# CMP_1_1.net
KiCad netlist of a schematic drawn in EAGLE
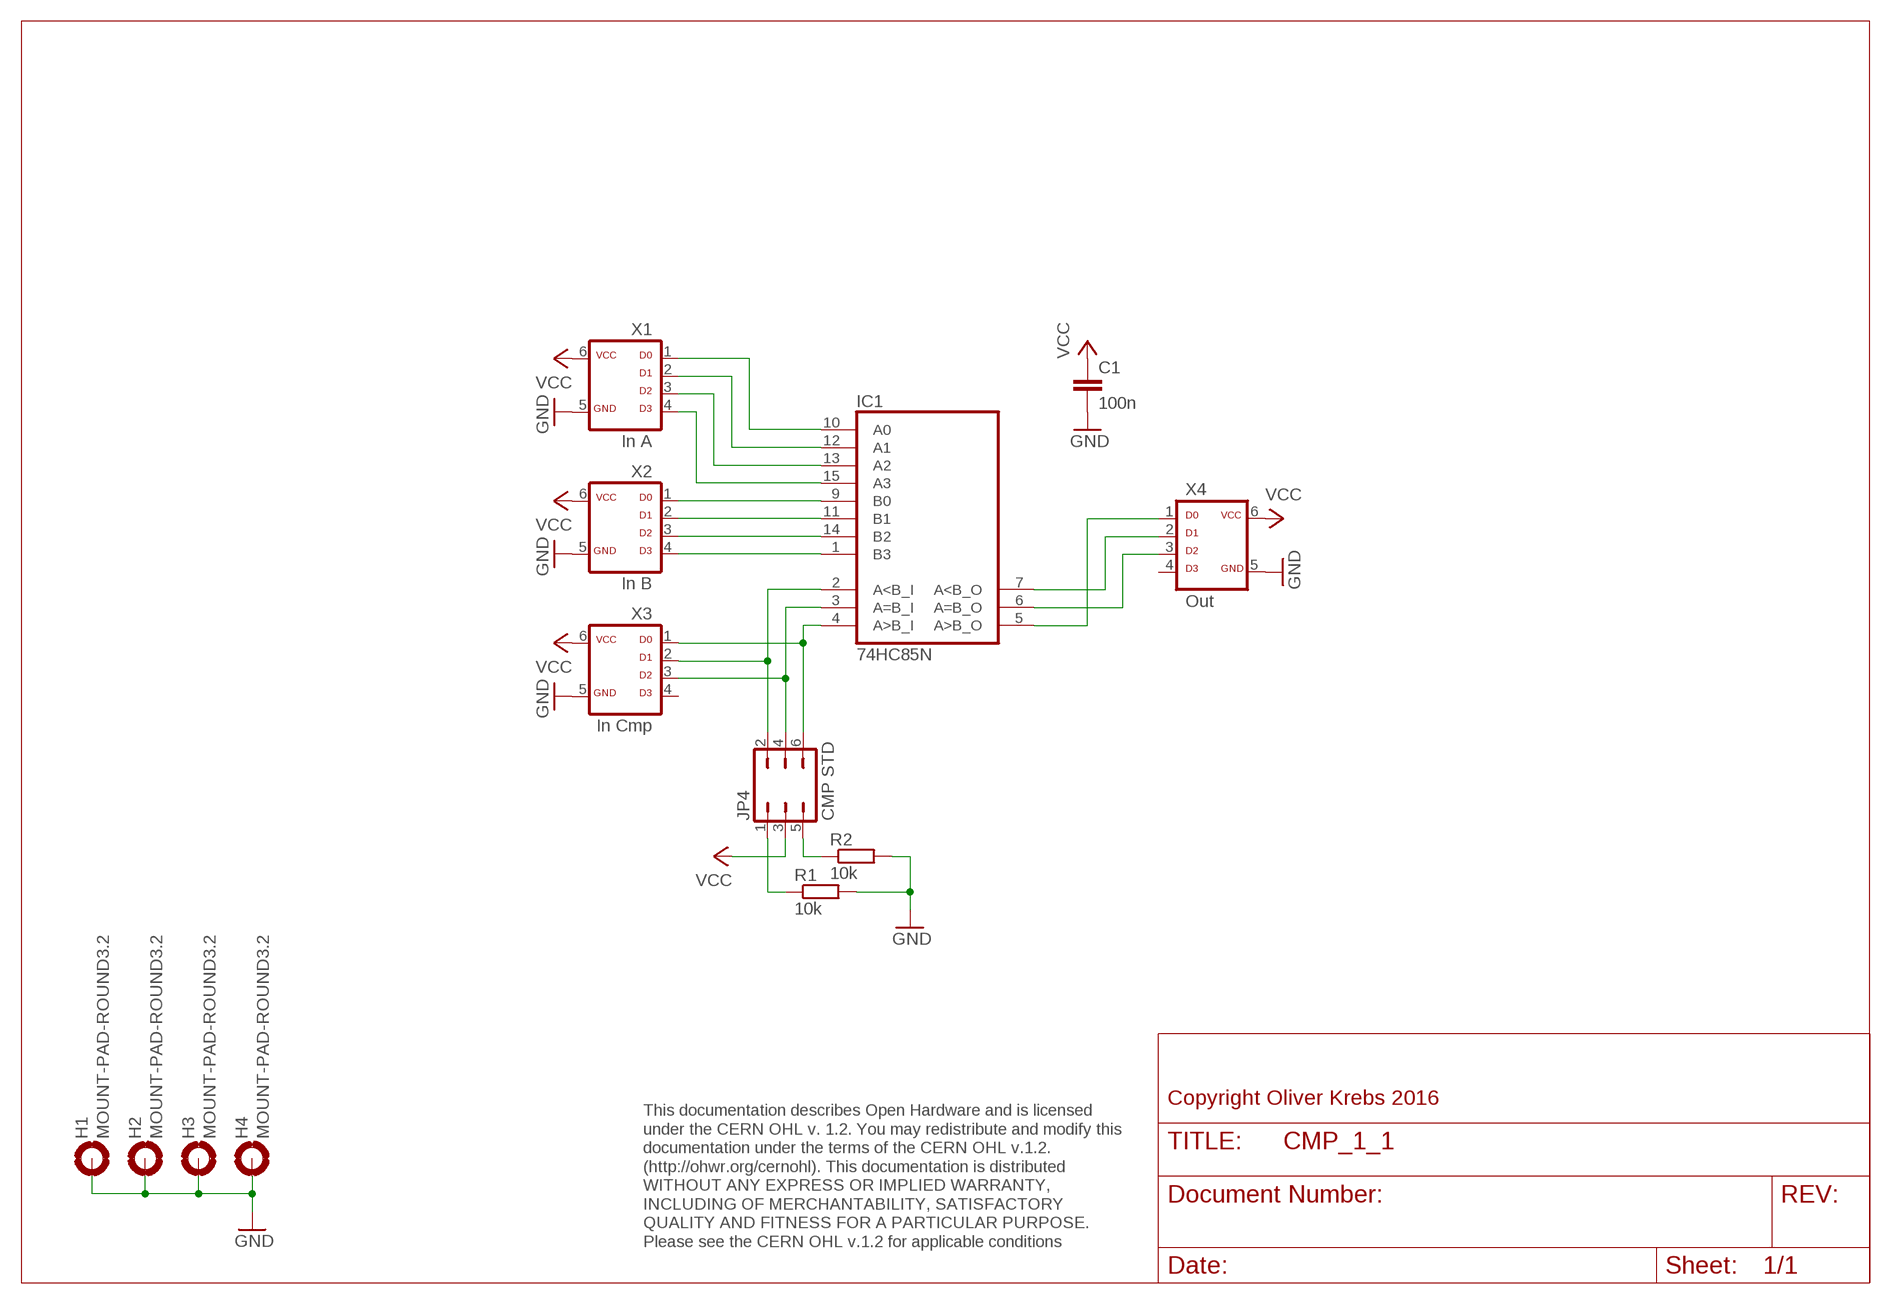
[diagram p0: schematic, sheet 1]

(export (version "E")
  (design (tool "Eeschema 10.0.6"))
  (components
    (comp (ref "C1")
      (value "100n")
      (footprint "eagle-import:C050-025X075")
      (libsource (lib "eagle-import") (part "C-EU050-025X075"))
    )
    (comp (ref "H1")
      (value "MOUNT-PAD-ROUND3.2")
      (footprint "eagle-import:3,2-PAD")
      (libsource (lib "eagle-import") (part "MOUNT-PAD-ROUND3.2"))
    )
    (comp (ref "H2")
      (value "MOUNT-PAD-ROUND3.2")
      (footprint "eagle-import:3,2-PAD")
      (libsource (lib "eagle-import") (part "MOUNT-PAD-ROUND3.2"))
    )
    (comp (ref "H3")
      (value "MOUNT-PAD-ROUND3.2")
      (footprint "eagle-import:3,2-PAD")
      (libsource (lib "eagle-import") (part "MOUNT-PAD-ROUND3.2"))
    )
    (comp (ref "H4")
      (value "MOUNT-PAD-ROUND3.2")
      (footprint "eagle-import:3,2-PAD")
      (libsource (lib "eagle-import") (part "MOUNT-PAD-ROUND3.2"))
    )
    (comp (ref "IC1")
      (value "74HC85N")
      (footprint "eagle-import:DIL16")
      (libsource (lib "eagle-import") (part "7485NHC"))
    )
    (comp (ref "JP4")
      (value "CMP STD")
      (footprint "eagle-import:JP3Q")
      (libsource (lib "eagle-import") (part "JP3Q"))
    )
    (comp (ref "R1")
      (value "10k")
      (footprint "eagle-import:0207_10")
      (libsource (lib "eagle-import") (part "R-EU_0207/10"))
    )
    (comp (ref "R2")
      (value "10k")
      (footprint "eagle-import:0207_10")
      (libsource (lib "eagle-import") (part "R-EU_0207/10"))
    )
    (comp (ref "X1")
      (value "In A")
      (footprint "eagle-import:ML-6")
      (libsource (lib "eagle-import") (part "ML6D"))
    )
    (comp (ref "X2")
      (value "In B")
      (footprint "eagle-import:ML-6")
      (libsource (lib "eagle-import") (part "ML6D"))
    )
    (comp (ref "X3")
      (value "In Cmp")
      (footprint "eagle-import:ML-6")
      (libsource (lib "eagle-import") (part "ML6D"))
    )
    (comp (ref "X4")
      (value "Out")
      (footprint "eagle-import:ML-6")
      (libsource (lib "eagle-import") (part "ML6D"))
    )
  )
  (nets
    (net (code "1") (name "GND") (class "Default")
      (node (ref "C1") (pin "2") (pinfunction "2_2") (pintype "passive"))
      (node (ref "H1") (pin "B3,2") (pinfunction "MOUNT_B3,2") (pintype "passive"))
      (node (ref "H2") (pin "B3,2") (pinfunction "MOUNT_B3,2") (pintype "passive"))
      (node (ref "H3") (pin "B3,2") (pinfunction "MOUNT_B3,2") (pintype "passive"))
      (node (ref "H4") (pin "B3,2") (pinfunction "MOUNT_B3,2") (pintype "passive"))
      (node (ref "R1") (pin "2") (pinfunction "2_2") (pintype "passive"))
      (node (ref "R2") (pin "2") (pinfunction "2_2") (pintype "passive"))
      (node (ref "X1") (pin "5") (pinfunction "5_5") (pintype "passive"))
      (node (ref "X2") (pin "5") (pinfunction "5_5") (pintype "passive"))
      (node (ref "X3") (pin "5") (pinfunction "5_5") (pintype "passive"))
      (node (ref "X4") (pin "5") (pinfunction "5_5") (pintype "passive"))
    )
    (net (code "2") (name "Net-(IC1A-A0)") (class "Default")
      (node (ref "IC1") (pin "10") (pinfunction "A0_10") (pintype "input"))
      (node (ref "X1") (pin "1") (pinfunction "1_1") (pintype "passive"))
    )
    (net (code "3") (name "Net-(IC1A-A1)") (class "Default")
      (node (ref "IC1") (pin "12") (pinfunction "A1_12") (pintype "input"))
      (node (ref "X1") (pin "2") (pinfunction "2_2") (pintype "passive"))
    )
    (net (code "4") (name "Net-(IC1A-A2)") (class "Default")
      (node (ref "IC1") (pin "13") (pinfunction "A2_13") (pintype "input"))
      (node (ref "X1") (pin "3") (pinfunction "3_3") (pintype "passive"))
    )
    (net (code "5") (name "Net-(IC1A-A3)") (class "Default")
      (node (ref "IC1") (pin "15") (pinfunction "A3_15") (pintype "input"))
      (node (ref "X1") (pin "4") (pinfunction "4_4") (pintype "passive"))
    )
    (net (code "6") (name "Net-(IC1A-A<B_I)") (class "Default")
      (node (ref "IC1") (pin "2") (pinfunction "A<B_I_2") (pintype "input"))
      (node (ref "JP4") (pin "2") (pinfunction "2_2") (pintype "passive"))
      (node (ref "X3") (pin "2") (pinfunction "2_2") (pintype "passive"))
    )
    (net (code "7") (name "Net-(IC1A-A<B_O)") (class "Default")
      (node (ref "IC1") (pin "7") (pinfunction "A<B_O_7") (pintype "output"))
      (node (ref "X4") (pin "2") (pinfunction "2_2") (pintype "passive"))
    )
    (net (code "8") (name "Net-(IC1A-A=B_I)") (class "Default")
      (node (ref "IC1") (pin "3") (pinfunction "A=B_I_3") (pintype "input"))
      (node (ref "JP4") (pin "4") (pinfunction "4_4") (pintype "passive"))
      (node (ref "X3") (pin "3") (pinfunction "3_3") (pintype "passive"))
    )
    (net (code "9") (name "Net-(IC1A-A=B_O)") (class "Default")
      (node (ref "IC1") (pin "6") (pinfunction "A=B_O_6") (pintype "output"))
      (node (ref "X4") (pin "3") (pinfunction "3_3") (pintype "passive"))
    )
    (net (code "10") (name "Net-(IC1A-A>B_I)") (class "Default")
      (node (ref "IC1") (pin "4") (pinfunction "A>B_I_4") (pintype "input"))
      (node (ref "JP4") (pin "6") (pinfunction "6_6") (pintype "passive"))
      (node (ref "X3") (pin "1") (pinfunction "1_1") (pintype "passive"))
    )
    (net (code "11") (name "Net-(IC1A-A>B_O)") (class "Default")
      (node (ref "IC1") (pin "5") (pinfunction "A>B_O_5") (pintype "output"))
      (node (ref "X4") (pin "1") (pinfunction "1_1") (pintype "passive"))
    )
    (net (code "12") (name "Net-(IC1A-B0)") (class "Default")
      (node (ref "IC1") (pin "9") (pinfunction "B0_9") (pintype "input"))
      (node (ref "X2") (pin "1") (pinfunction "1_1") (pintype "passive"))
    )
    (net (code "13") (name "Net-(IC1A-B1)") (class "Default")
      (node (ref "IC1") (pin "11") (pinfunction "B1_11") (pintype "input"))
      (node (ref "X2") (pin "2") (pinfunction "2_2") (pintype "passive"))
    )
    (net (code "14") (name "Net-(IC1A-B2)") (class "Default")
      (node (ref "IC1") (pin "14") (pinfunction "B2_14") (pintype "input"))
      (node (ref "X2") (pin "3") (pinfunction "3_3") (pintype "passive"))
    )
    (net (code "15") (name "Net-(IC1A-B3)") (class "Default")
      (node (ref "IC1") (pin "1") (pinfunction "B3_1") (pintype "input"))
      (node (ref "X2") (pin "4") (pinfunction "4_4") (pintype "passive"))
    )
    (net (code "16") (name "Net-(JP4-Pad1)") (class "Default")
      (node (ref "JP4") (pin "1") (pinfunction "1_1") (pintype "passive"))
      (node (ref "R1") (pin "1") (pinfunction "1_1") (pintype "passive"))
    )
    (net (code "17") (name "Net-(JP4-Pad5)") (class "Default")
      (node (ref "JP4") (pin "5") (pinfunction "5_5") (pintype "passive"))
      (node (ref "R2") (pin "1") (pinfunction "1_1") (pintype "passive"))
    )
    (net (code "18") (name "VCC") (class "Default")
      (node (ref "C1") (pin "1") (pinfunction "1_1") (pintype "passive"))
      (node (ref "JP4") (pin "3") (pinfunction "3_3") (pintype "passive"))
      (node (ref "X1") (pin "6") (pinfunction "6_6") (pintype "passive"))
      (node (ref "X2") (pin "6") (pinfunction "6_6") (pintype "passive"))
      (node (ref "X3") (pin "6") (pinfunction "6_6") (pintype "passive"))
      (node (ref "X4") (pin "6") (pinfunction "6_6") (pintype "passive"))
    )
    (net (code "19") (name "unconnected-(X3-Pad4)") (class "Default")
      (node (ref "X3") (pin "4") (pinfunction "4_4") (pintype "passive"))
    )
    (net (code "20") (name "unconnected-(X4-Pad4)") (class "Default")
      (node (ref "X4") (pin "4") (pinfunction "4_4") (pintype "passive"))
    )
  )
)
